# StarvingStudent.net
KiCad netlist of a schematic drawn in EAGLE
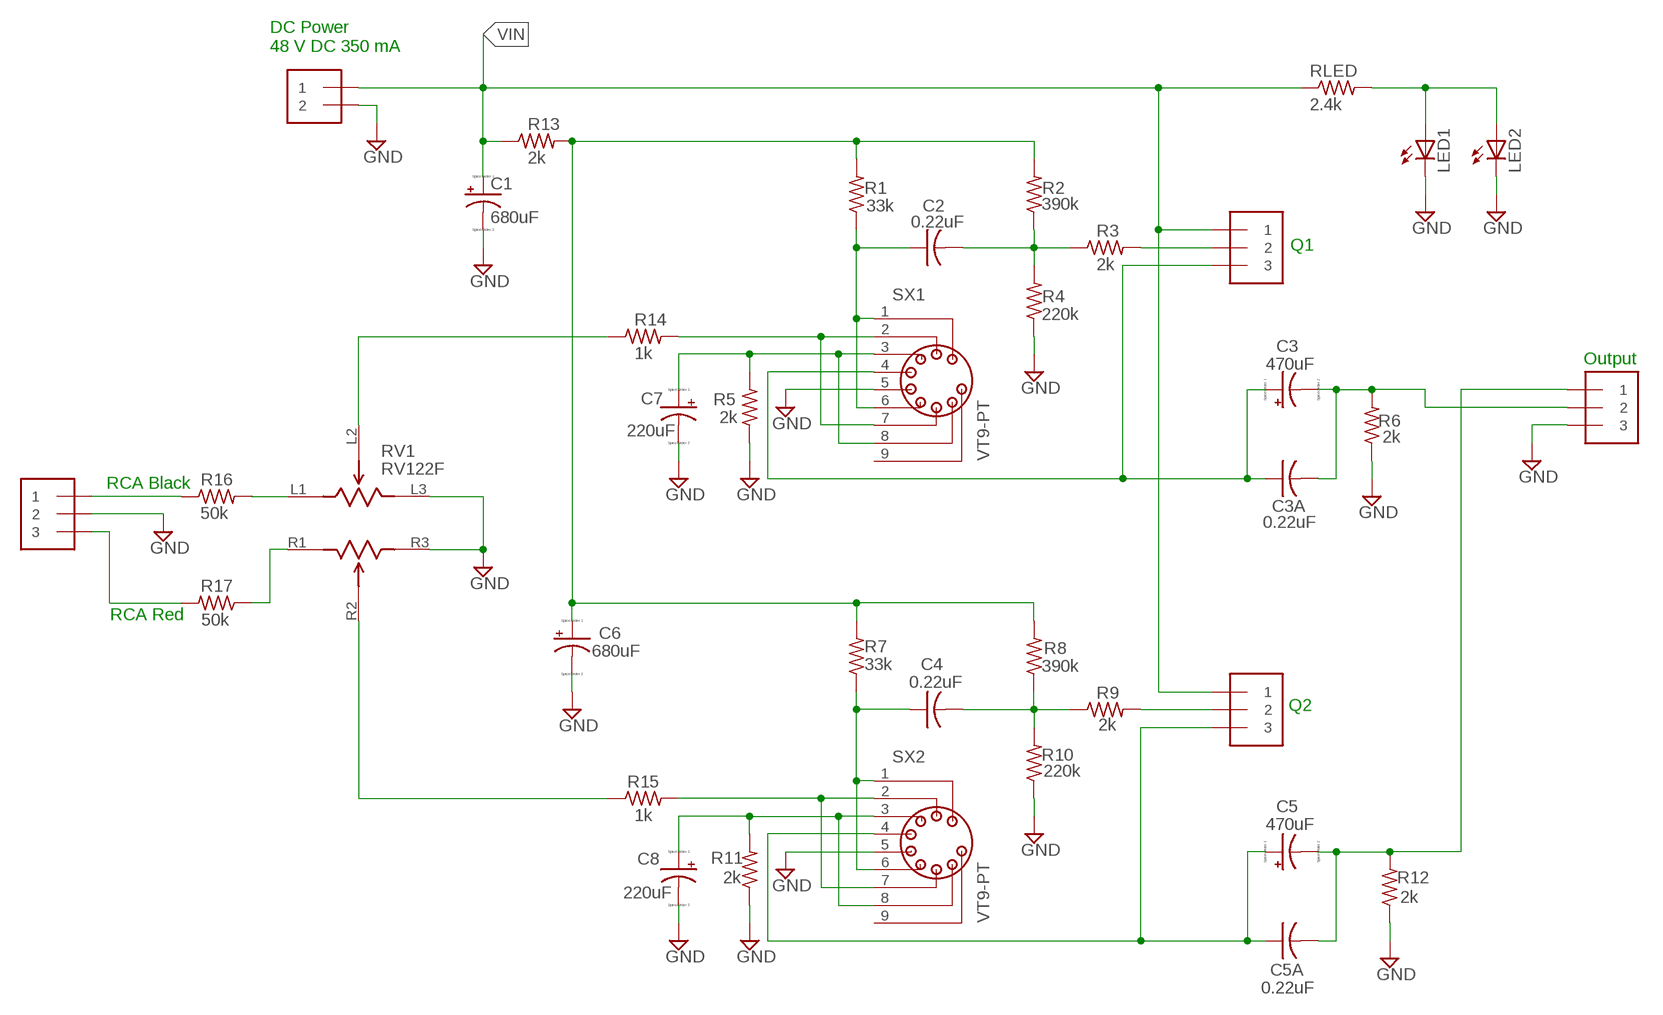
[diagram p0: schematic, sheet 1]

(export (version "E")
  (design (tool "Eeschema 10.0.6"))
  (components
    (comp (ref "C1")
      (value "680uF")
      (footprint "eagle-import:E7,5-18")
      (libsource (lib "eagle-import") (part "CPOL-USE7.5-18"))
    )
    (comp (ref "C2")
      (value "0.22uF")
      (footprint "eagle-import:C150-072X183")
      (libsource (lib "eagle-import") (part "C-US150-072X183"))
    )
    (comp (ref "C3")
      (value "470uF")
      (footprint "eagle-import:E5-13")
      (libsource (lib "eagle-import") (part "CPOL-USE5-13"))
    )
    (comp (ref "C3A")
      (value "0.22uF")
      (footprint "eagle-import:C150-072X183")
      (libsource (lib "eagle-import") (part "C-US150-072X183"))
    )
    (comp (ref "C4")
      (value "0.22uF")
      (footprint "eagle-import:C150-072X183")
      (libsource (lib "eagle-import") (part "C-US150-072X183"))
    )
    (comp (ref "C5")
      (value "470uF")
      (footprint "eagle-import:E5-13")
      (libsource (lib "eagle-import") (part "CPOL-USE5-13"))
    )
    (comp (ref "C5A")
      (value "0.22uF")
      (footprint "eagle-import:C150-072X183")
      (libsource (lib "eagle-import") (part "C-US150-072X183"))
    )
    (comp (ref "C6")
      (value "680uF")
      (footprint "eagle-import:E7,5-18")
      (libsource (lib "eagle-import") (part "CPOL-USE7.5-18"))
    )
    (comp (ref "C7")
      (value "220uF")
      (footprint "eagle-import:E5-13")
      (libsource (lib "eagle-import") (part "CPOL-USE5-13"))
    )
    (comp (ref "C8")
      (value "220uF")
      (footprint "eagle-import:E5-13")
      (libsource (lib "eagle-import") (part "CPOL-USE5-13"))
    )
    (comp (ref "J1")
      (value "1X2-3.5MM")
      (footprint "eagle-import:1X2-3.5MM")
      (libsource (lib "eagle-import") (part "1X2-3.5MM"))
    )
    (comp (ref "J2")
      (value "1X3-3.5MM")
      (footprint "eagle-import:1X3-3.5MM")
      (libsource (lib "eagle-import") (part "1X3-3.5MM"))
    )
    (comp (ref "J3")
      (value "1X3-3.5MM")
      (footprint "eagle-import:1X3-3.5MM")
      (libsource (lib "eagle-import") (part "1X3-3.5MM"))
    )
    (comp (ref "J4")
      (value "1X3-3.5MM")
      (footprint "eagle-import:1X3-3.5MM")
      (libsource (lib "eagle-import") (part "1X3-3.5MM"))
    )
    (comp (ref "J5")
      (value "1X3-3.5MM")
      (footprint "eagle-import:1X3-3.5MM")
      (libsource (lib "eagle-import") (part "1X3-3.5MM"))
    )
    (comp (ref "LED1")
      (value "LED3MM")
      (footprint "eagle-import:LED3MM")
      (libsource (lib "eagle-import") (part "LED3MM"))
    )
    (comp (ref "LED2")
      (value "LED3MM")
      (footprint "eagle-import:LED3MM")
      (libsource (lib "eagle-import") (part "LED3MM"))
    )
    (comp (ref "R1")
      (value "33k")
      (footprint "eagle-import:0207_10")
      (libsource (lib "eagle-import") (part "R-US_0207/10"))
    )
    (comp (ref "R2")
      (value "390k")
      (footprint "eagle-import:0207_10")
      (libsource (lib "eagle-import") (part "R-US_0207/10"))
    )
    (comp (ref "R3")
      (value "2k")
      (footprint "eagle-import:0207_10")
      (libsource (lib "eagle-import") (part "R-US_0207/10"))
    )
    (comp (ref "R4")
      (value "220k")
      (footprint "eagle-import:0207_10")
      (libsource (lib "eagle-import") (part "R-US_0207/10"))
    )
    (comp (ref "R5")
      (value "2k")
      (footprint "eagle-import:0207_10")
      (libsource (lib "eagle-import") (part "R-US_0207/10"))
    )
    (comp (ref "R6")
      (value "2k")
      (footprint "eagle-import:0207_10")
      (libsource (lib "eagle-import") (part "R-US_0207/10"))
    )
    (comp (ref "R7")
      (value "33k")
      (footprint "eagle-import:0207_10")
      (libsource (lib "eagle-import") (part "R-US_0207/10"))
    )
    (comp (ref "R8")
      (value "390k")
      (footprint "eagle-import:0207_10")
      (libsource (lib "eagle-import") (part "R-US_0207/10"))
    )
    (comp (ref "R9")
      (value "2k")
      (footprint "eagle-import:0207_10")
      (libsource (lib "eagle-import") (part "R-US_0207/10"))
    )
    (comp (ref "R10")
      (value "220k")
      (footprint "eagle-import:0207_10")
      (libsource (lib "eagle-import") (part "R-US_0207/10"))
    )
    (comp (ref "R11")
      (value "2k")
      (footprint "eagle-import:0207_10")
      (libsource (lib "eagle-import") (part "R-US_0207/10"))
    )
    (comp (ref "R12")
      (value "2k")
      (footprint "eagle-import:0207_10")
      (libsource (lib "eagle-import") (part "R-US_0207/10"))
    )
    (comp (ref "R13")
      (value "2k")
      (footprint "eagle-import:0207_10")
      (libsource (lib "eagle-import") (part "R-US_0207/10"))
    )
    (comp (ref "R14")
      (value "1k")
      (footprint "eagle-import:0207_10")
      (libsource (lib "eagle-import") (part "R-US_0207/10"))
    )
    (comp (ref "R15")
      (value "1k")
      (footprint "eagle-import:0207_10")
      (libsource (lib "eagle-import") (part "R-US_0207/10"))
    )
    (comp (ref "R16")
      (value "50k")
      (footprint "eagle-import:0207_10")
      (libsource (lib "eagle-import") (part "R-US_0207/10"))
    )
    (comp (ref "R17")
      (value "50k")
      (footprint "eagle-import:0207_10")
      (libsource (lib "eagle-import") (part "R-US_0207/10"))
    )
    (comp (ref "RLED")
      (value "2.4k")
      (footprint "eagle-import:0411_15")
      (libsource (lib "eagle-import") (part "R-US_0411/15"))
    )
    (comp (ref "RV1")
      (value "RV122F")
      (footprint "eagle-import:RV122F")
      (libsource (lib "eagle-import") (part "RV122F"))
    )
    (comp (ref "SX1")
      (value "VT9-PT")
      (footprint "eagle-import:VT9-PT")
      (libsource (lib "eagle-import") (part "VT9-PT"))
    )
    (comp (ref "SX2")
      (value "VT9-PT")
      (footprint "eagle-import:VT9-PT")
      (libsource (lib "eagle-import") (part "VT9-PT"))
    )
  )
  (nets
    (net (code "1") (name "GND") (class "Default")
      (node (ref "C1") (pin "-") (pinfunction "-_-") (pintype "passive"))
      (node (ref "C6") (pin "-") (pinfunction "-_-") (pintype "passive"))
      (node (ref "C7") (pin "-") (pinfunction "-_-") (pintype "passive"))
      (node (ref "C8") (pin "-") (pinfunction "-_-") (pintype "passive"))
      (node (ref "J1") (pin "2") (pinfunction "2_2") (pintype "passive"))
      (node (ref "J2") (pin "2") (pinfunction "2_2") (pintype "passive"))
      (node (ref "J5") (pin "1") (pinfunction "3_1") (pintype "passive"))
      (node (ref "LED1") (pin "K") (pinfunction "C_K") (pintype "passive"))
      (node (ref "LED2") (pin "K") (pinfunction "C_K") (pintype "passive"))
      (node (ref "R10") (pin "1") (pinfunction "1_1") (pintype "passive"))
      (node (ref "R11") (pin "1") (pinfunction "1_1") (pintype "passive"))
      (node (ref "R12") (pin "1") (pinfunction "1_1") (pintype "passive"))
      (node (ref "R4") (pin "1") (pinfunction "1_1") (pintype "passive"))
      (node (ref "R5") (pin "1") (pinfunction "1_1") (pintype "passive"))
      (node (ref "R6") (pin "1") (pinfunction "1_1") (pintype "passive"))
      (node (ref "RV1") (pin "L3") (pinfunction "L3_L3") (pintype "bidirectional"))
      (node (ref "RV1") (pin "R3") (pinfunction "R3_R3") (pintype "bidirectional"))
      (node (ref "SX1") (pin "5") (pinfunction "5_5") (pintype "passive"))
      (node (ref "SX2") (pin "5") (pinfunction "5_5") (pintype "passive"))
    )
    (net (code "2") (name "Net-(C2-Pad1)") (class "Default")
      (node (ref "C2") (pin "1") (pinfunction "1_1") (pintype "passive"))
      (node (ref "R1") (pin "1") (pinfunction "1_1") (pintype "passive"))
      (node (ref "SX1") (pin "1") (pinfunction "1_1") (pintype "passive"))
      (node (ref "SX1") (pin "6") (pinfunction "6_6") (pintype "passive"))
    )
    (net (code "3") (name "Net-(C2-Pad2)") (class "Default")
      (node (ref "C2") (pin "2") (pinfunction "2_2") (pintype "passive"))
      (node (ref "R2") (pin "1") (pinfunction "1_1") (pintype "passive"))
      (node (ref "R3") (pin "1") (pinfunction "1_1") (pintype "passive"))
      (node (ref "R4") (pin "2") (pinfunction "2_2") (pintype "passive"))
    )
    (net (code "4") (name "Net-(C3-Pad-)") (class "Default")
      (node (ref "C3") (pin "-") (pinfunction "-_-") (pintype "passive"))
      (node (ref "C3A") (pin "2") (pinfunction "2_2") (pintype "passive"))
      (node (ref "J5") (pin "2") (pinfunction "2_2") (pintype "passive"))
      (node (ref "R6") (pin "2") (pinfunction "2_2") (pintype "passive"))
    )
    (net (code "5") (name "Net-(C4-Pad1)") (class "Default")
      (node (ref "C4") (pin "1") (pinfunction "1_1") (pintype "passive"))
      (node (ref "R7") (pin "1") (pinfunction "1_1") (pintype "passive"))
      (node (ref "SX2") (pin "1") (pinfunction "1_1") (pintype "passive"))
      (node (ref "SX2") (pin "6") (pinfunction "6_6") (pintype "passive"))
    )
    (net (code "6") (name "Net-(C4-Pad2)") (class "Default")
      (node (ref "C4") (pin "2") (pinfunction "2_2") (pintype "passive"))
      (node (ref "R10") (pin "2") (pinfunction "2_2") (pintype "passive"))
      (node (ref "R8") (pin "1") (pinfunction "1_1") (pintype "passive"))
      (node (ref "R9") (pin "1") (pinfunction "1_1") (pintype "passive"))
    )
    (net (code "7") (name "Net-(C6-Pad+)") (class "Default")
      (node (ref "C6") (pin "+") (pinfunction "+_+") (pintype "passive"))
      (node (ref "R1") (pin "2") (pinfunction "2_2") (pintype "passive"))
      (node (ref "R13") (pin "2") (pinfunction "2_2") (pintype "passive"))
      (node (ref "R2") (pin "2") (pinfunction "2_2") (pintype "passive"))
      (node (ref "R7") (pin "2") (pinfunction "2_2") (pintype "passive"))
      (node (ref "R8") (pin "2") (pinfunction "2_2") (pintype "passive"))
    )
    (net (code "8") (name "Net-(C7-Pad+)") (class "Default")
      (node (ref "C7") (pin "+") (pinfunction "+_+") (pintype "passive"))
      (node (ref "R5") (pin "2") (pinfunction "2_2") (pintype "passive"))
      (node (ref "SX1") (pin "3") (pinfunction "3_3") (pintype "passive"))
      (node (ref "SX1") (pin "8") (pinfunction "8_8") (pintype "passive"))
    )
    (net (code "9") (name "Net-(C8-Pad+)") (class "Default")
      (node (ref "C8") (pin "+") (pinfunction "+_+") (pintype "passive"))
      (node (ref "R11") (pin "2") (pinfunction "2_2") (pintype "passive"))
      (node (ref "SX2") (pin "3") (pinfunction "3_3") (pintype "passive"))
      (node (ref "SX2") (pin "8") (pinfunction "8_8") (pintype "passive"))
    )
    (net (code "10") (name "Net-(J2-1)") (class "Default")
      (node (ref "J2") (pin "3") (pinfunction "1_3") (pintype "passive"))
      (node (ref "R16") (pin "1") (pinfunction "1_1") (pintype "passive"))
    )
    (net (code "11") (name "Net-(J2-3)") (class "Default")
      (node (ref "J2") (pin "1") (pinfunction "3_1") (pintype "passive"))
      (node (ref "R17") (pin "2") (pinfunction "2_2") (pintype "passive"))
    )
    (net (code "12") (name "Net-(J3-3)") (class "Default")
      (node (ref "C3") (pin "+") (pinfunction "+_+") (pintype "passive"))
      (node (ref "C3A") (pin "1") (pinfunction "1_1") (pintype "passive"))
      (node (ref "J3") (pin "1") (pinfunction "3_1") (pintype "passive"))
      (node (ref "SX1") (pin "4") (pinfunction "4_4") (pintype "passive"))
    )
    (net (code "13") (name "Net-(J3-Pad2)") (class "Default")
      (node (ref "J3") (pin "2") (pinfunction "2_2") (pintype "passive"))
      (node (ref "R3") (pin "2") (pinfunction "2_2") (pintype "passive"))
    )
    (net (code "14") (name "Net-(J4-3)") (class "Default")
      (node (ref "C5") (pin "+") (pinfunction "+_+") (pintype "passive"))
      (node (ref "C5A") (pin "1") (pinfunction "1_1") (pintype "passive"))
      (node (ref "J4") (pin "1") (pinfunction "3_1") (pintype "passive"))
      (node (ref "SX2") (pin "4") (pinfunction "4_4") (pintype "passive"))
    )
    (net (code "15") (name "Net-(J4-Pad2)") (class "Default")
      (node (ref "J4") (pin "2") (pinfunction "2_2") (pintype "passive"))
      (node (ref "R9") (pin "2") (pinfunction "2_2") (pintype "passive"))
    )
    (net (code "16") (name "Net-(J5-1)") (class "Default")
      (node (ref "C5") (pin "-") (pinfunction "-_-") (pintype "passive"))
      (node (ref "C5A") (pin "2") (pinfunction "2_2") (pintype "passive"))
      (node (ref "J5") (pin "3") (pinfunction "1_3") (pintype "passive"))
      (node (ref "R12") (pin "2") (pinfunction "2_2") (pintype "passive"))
    )
    (net (code "17") (name "Net-(LED1-PadA)") (class "Default")
      (node (ref "LED1") (pin "A") (pinfunction "A_A") (pintype "passive"))
      (node (ref "LED2") (pin "A") (pinfunction "A_A") (pintype "passive"))
      (node (ref "RLED") (pin "2") (pinfunction "2_2") (pintype "passive"))
    )
    (net (code "18") (name "Net-(R14-Pad1)") (class "Default")
      (node (ref "R14") (pin "1") (pinfunction "1_1") (pintype "passive"))
      (node (ref "RV1") (pin "L2") (pinfunction "L2_L2") (pintype "bidirectional"))
    )
    (net (code "19") (name "Net-(R14-Pad2)") (class "Default")
      (node (ref "R14") (pin "2") (pinfunction "2_2") (pintype "passive"))
      (node (ref "SX1") (pin "2") (pinfunction "2_2") (pintype "passive"))
      (node (ref "SX1") (pin "7") (pinfunction "7_7") (pintype "passive"))
    )
    (net (code "20") (name "Net-(R15-Pad1)") (class "Default")
      (node (ref "R15") (pin "1") (pinfunction "1_1") (pintype "passive"))
      (node (ref "RV1") (pin "R2") (pinfunction "R2_R2") (pintype "bidirectional"))
    )
    (net (code "21") (name "Net-(R15-Pad2)") (class "Default")
      (node (ref "R15") (pin "2") (pinfunction "2_2") (pintype "passive"))
      (node (ref "SX2") (pin "2") (pinfunction "2_2") (pintype "passive"))
      (node (ref "SX2") (pin "7") (pinfunction "7_7") (pintype "passive"))
    )
    (net (code "22") (name "Net-(R16-Pad2)") (class "Default")
      (node (ref "R16") (pin "2") (pinfunction "2_2") (pintype "passive"))
      (node (ref "RV1") (pin "L1") (pinfunction "L1_L1") (pintype "bidirectional"))
    )
    (net (code "23") (name "Net-(R17-Pad1)") (class "Default")
      (node (ref "R17") (pin "1") (pinfunction "1_1") (pintype "passive"))
      (node (ref "RV1") (pin "R1") (pinfunction "R1_R1") (pintype "bidirectional"))
    )
    (net (code "24") (name "VIN") (class "Default")
      (node (ref "C1") (pin "+") (pinfunction "+_+") (pintype "passive"))
      (node (ref "J1") (pin "1") (pinfunction "1_1") (pintype "passive"))
      (node (ref "J3") (pin "3") (pinfunction "1_3") (pintype "passive"))
      (node (ref "J4") (pin "3") (pinfunction "1_3") (pintype "passive"))
      (node (ref "R13") (pin "1") (pinfunction "1_1") (pintype "passive"))
      (node (ref "RLED") (pin "1") (pinfunction "1_1") (pintype "passive"))
    )
    (net (code "25") (name "unconnected-(SX1-Pad9)") (class "Default")
      (node (ref "SX1") (pin "9") (pinfunction "9_9") (pintype "passive"))
    )
    (net (code "26") (name "unconnected-(SX2-Pad9)") (class "Default")
      (node (ref "SX2") (pin "9") (pinfunction "9_9") (pintype "passive"))
    )
  )
)
